# dnc_titreur.net
KiCad netlist of a schematic drawn in EAGLE
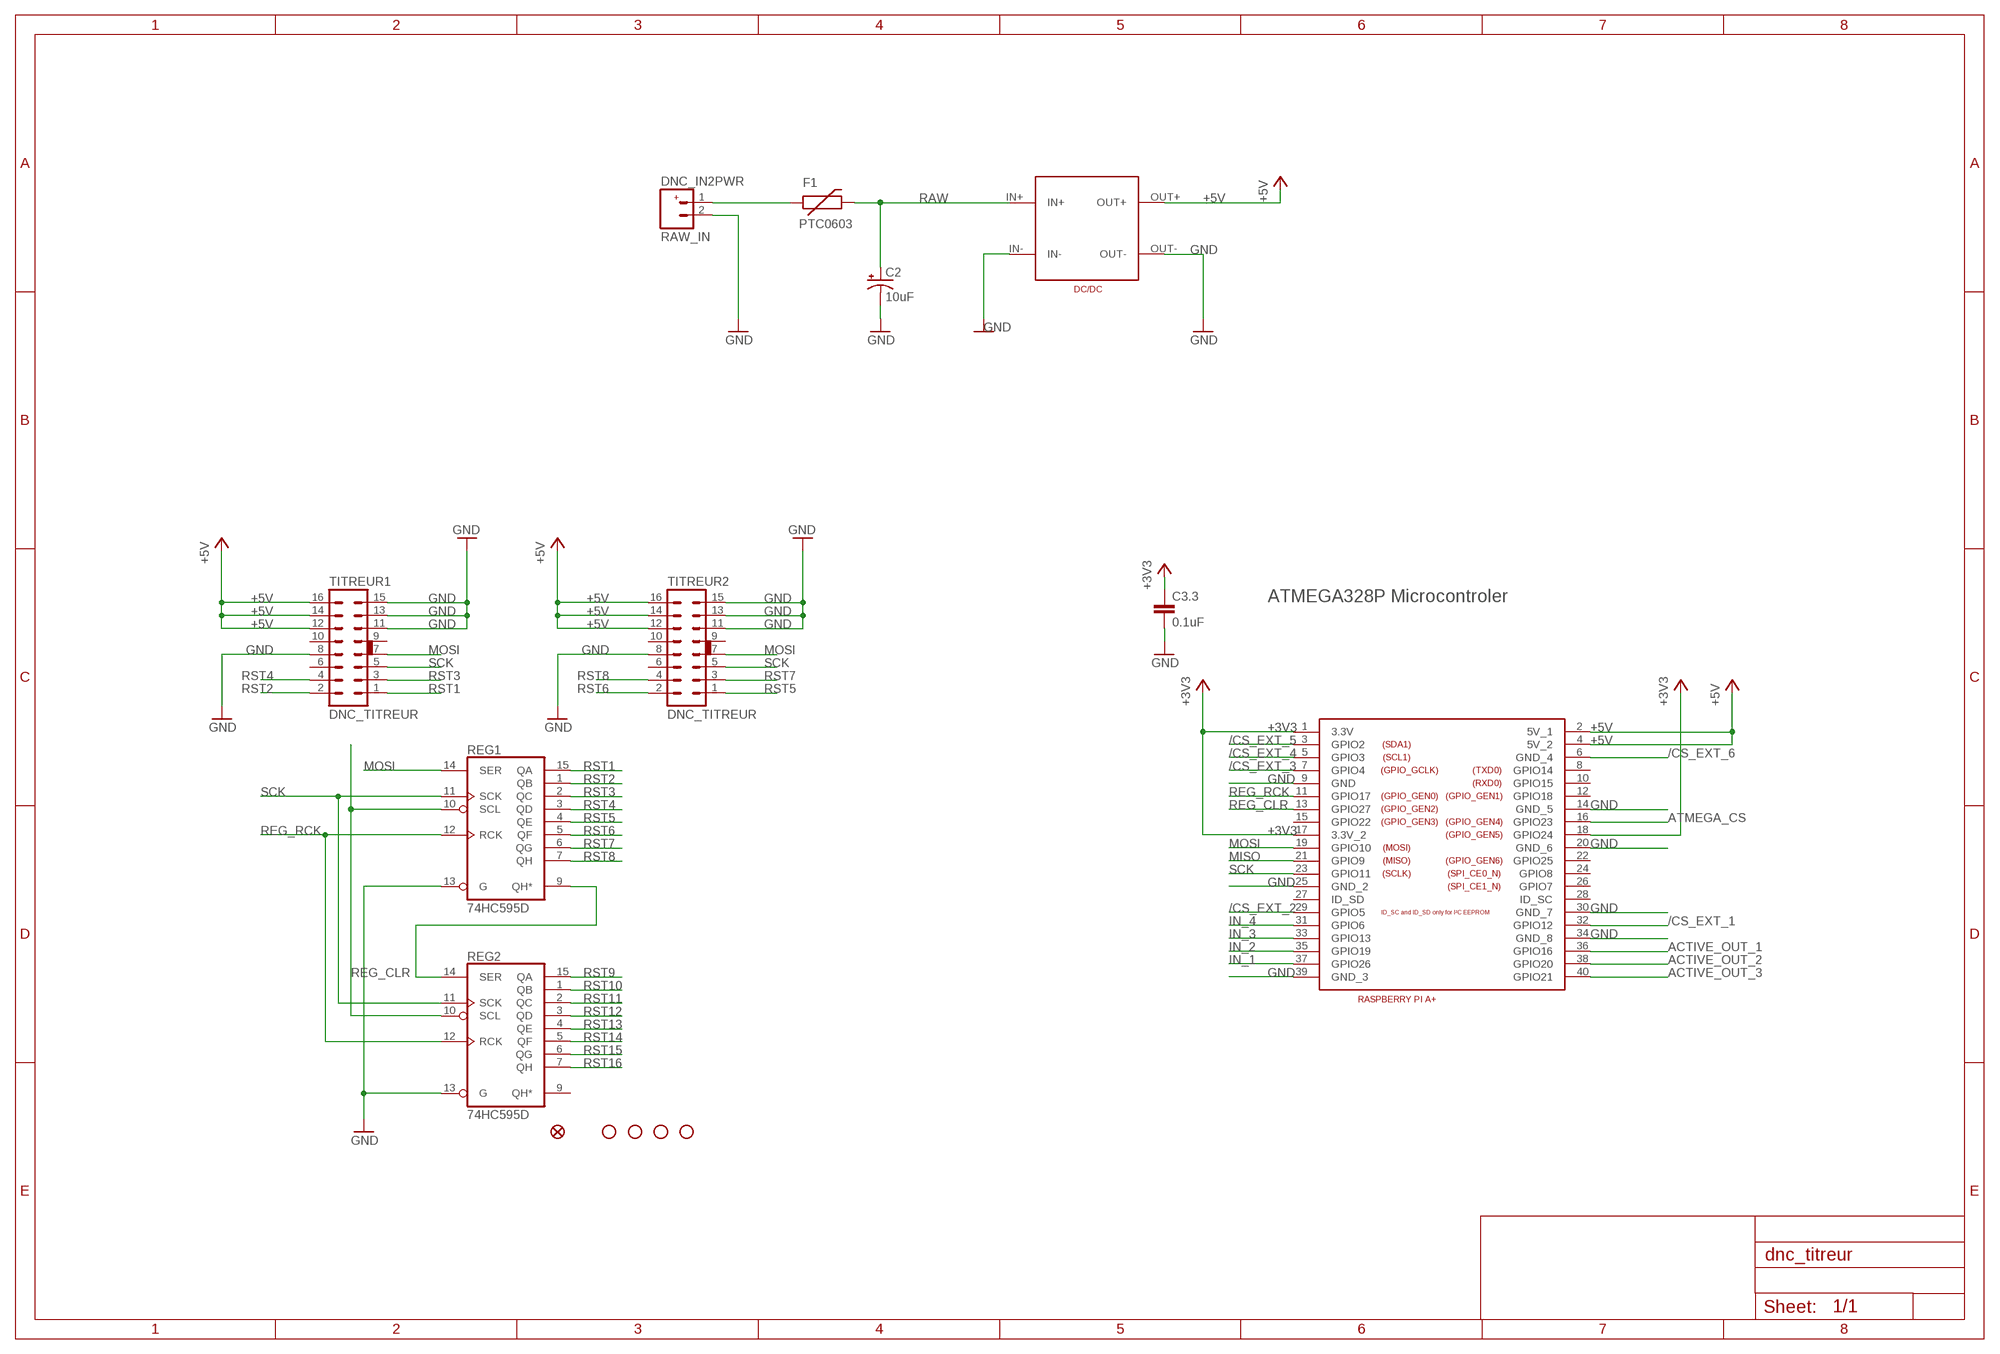
[diagram p0: schematic, sheet 1]

(export (version "E")
  (design (tool "Eeschema 10.0.6"))
  (components
    (comp (ref "C2")
      (value "10uF")
      (footprint "eagle-import:EIA3216")
      (libsource (lib "eagle-import") (part "CAP_POL1206"))
    )
    (comp (ref "C3.3")
      (value "0.1uF")
      (footprint "eagle-import:C0805")
      (libsource (lib "eagle-import") (part "C-EUC0805"))
    )
    (comp (ref "F1")
      (value "PTC0603")
      (footprint "eagle-import:0603")
      (libsource (lib "eagle-import") (part "PTC0603"))
    )
    (comp (ref "JP14")
      (value "FIDUCIAL1X2.5")
      (footprint "eagle-import:FIDUCIAL-1X2.5")
      (libsource (lib "eagle-import") (part "FIDUCIAL1X2.5"))
    )
    (comp (ref "JP15")
      (value "STAND-OFF")
      (footprint "eagle-import:STAND-OFF")
      (libsource (lib "eagle-import") (part "STAND-OFF"))
    )
    (comp (ref "JP16")
      (value "STAND-OFF")
      (footprint "eagle-import:STAND-OFF")
      (libsource (lib "eagle-import") (part "STAND-OFF"))
    )
    (comp (ref "JP17")
      (value "STAND-OFF")
      (footprint "eagle-import:STAND-OFF")
      (libsource (lib "eagle-import") (part "STAND-OFF"))
    )
    (comp (ref "JP18")
      (value "STAND-OFF")
      (footprint "eagle-import:STAND-OFF")
      (libsource (lib "eagle-import") (part "STAND-OFF"))
    )
    (comp (ref "RAW_IN")
      (value "DNC_IN2PWR")
      (footprint "eagle-import:DNC_IN2_PWR")
      (libsource (lib "eagle-import") (part "DNC_IN2PWR"))
    )
    (comp (ref "REG1")
      (value "74HC595D")
      (footprint "eagle-import:SO16")
      (libsource (lib "eagle-import") (part "74595DHC"))
    )
    (comp (ref "REG2")
      (value "74HC595D")
      (footprint "eagle-import:SO16")
      (libsource (lib "eagle-import") (part "74595DHC"))
    )
    (comp (ref "TITREUR1")
      (value "DNC_TITREUR")
      (footprint "eagle-import:DNC_TITREUR")
      (libsource (lib "eagle-import") (part "DNC_TITREUR"))
    )
    (comp (ref "TITREUR2")
      (value "DNC_TITREUR")
      (footprint "eagle-import:DNC_TITREUR")
      (libsource (lib "eagle-import") (part "DNC_TITREUR"))
    )
    (comp (ref "U$4")
      (value "RASPIA+")
      (footprint "eagle-import:RASPIA+")
      (libsource (lib "eagle-import") (part "RASPIA+"))
    )
    (comp (ref "U$5")
      (value "DC/DC_SEED")
      (footprint "eagle-import:DC_DC_SEED")
      (libsource (lib "eagle-import") (part "DC/DC_SEED"))
    )
  )
  (nets
    (net (code "1") (name "+3V3") (class "Default")
      (node (ref "C3.3") (pin "1") (pinfunction "1_1") (pintype "passive"))
      (node (ref "U$4") (pin "1") (pinfunction "3.3V_1") (pintype "bidirectional"))
      (node (ref "U$4") (pin "17") (pinfunction "3.3V_2_17") (pintype "bidirectional"))
      (node (ref "U$4") (pin "18") (pinfunction "GPIO24_18") (pintype "bidirectional"))
    )
    (net (code "2") (name "+5V") (class "Default")
      (node (ref "TITREUR1") (pin "12") (pinfunction "12_12") (pintype "passive"))
      (node (ref "TITREUR1") (pin "14") (pinfunction "14_14") (pintype "passive"))
      (node (ref "TITREUR1") (pin "16") (pinfunction "16_16") (pintype "passive"))
      (node (ref "TITREUR2") (pin "12") (pinfunction "12_12") (pintype "passive"))
      (node (ref "TITREUR2") (pin "14") (pinfunction "14_14") (pintype "passive"))
      (node (ref "TITREUR2") (pin "16") (pinfunction "16_16") (pintype "passive"))
      (node (ref "U$4") (pin "2") (pinfunction "5V_1_2") (pintype "bidirectional"))
      (node (ref "U$4") (pin "4") (pinfunction "5V_2_4") (pintype "bidirectional"))
      (node (ref "U$5") (pin "OUT+") (pinfunction "OUT+_OUT+") (pintype "bidirectional"))
    )
    (net (code "3") (name "/ACTIVE_OUT_1") (class "Default")
      (node (ref "U$4") (pin "36") (pinfunction "GPIO16_36") (pintype "bidirectional"))
    )
    (net (code "4") (name "/ACTIVE_OUT_2") (class "Default")
      (node (ref "U$4") (pin "38") (pinfunction "GPIO20_38") (pintype "bidirectional"))
    )
    (net (code "5") (name "/ACTIVE_OUT_3") (class "Default")
      (node (ref "U$4") (pin "40") (pinfunction "GPIO21_40") (pintype "bidirectional"))
    )
    (net (code "6") (name "/ATMEGA_CS") (class "Default")
      (node (ref "U$4") (pin "16") (pinfunction "GPIO23_16") (pintype "bidirectional"))
    )
    (net (code "7") (name "/IN_1") (class "Default")
      (node (ref "U$4") (pin "37") (pinfunction "GPIO26_37") (pintype "bidirectional"))
    )
    (net (code "8") (name "/IN_2") (class "Default")
      (node (ref "U$4") (pin "35") (pinfunction "GPIO19_35") (pintype "bidirectional"))
    )
    (net (code "9") (name "/IN_3") (class "Default")
      (node (ref "U$4") (pin "33") (pinfunction "GPIO13_33") (pintype "bidirectional"))
    )
    (net (code "10") (name "/IN_4") (class "Default")
      (node (ref "U$4") (pin "31") (pinfunction "GPIO6_31") (pintype "bidirectional"))
    )
    (net (code "11") (name "/MISO") (class "Default")
      (node (ref "U$4") (pin "21") (pinfunction "GPIO9_21") (pintype "bidirectional"))
    )
    (net (code "12") (name "/MOSI") (class "Default")
      (node (ref "REG1") (pin "14") (pinfunction "SER_14") (pintype "input"))
      (node (ref "TITREUR1") (pin "7") (pinfunction "7_7") (pintype "passive"))
      (node (ref "TITREUR2") (pin "7") (pinfunction "7_7") (pintype "passive"))
      (node (ref "U$4") (pin "19") (pinfunction "GPIO10_19") (pintype "bidirectional"))
    )
    (net (code "13") (name "/RAW") (class "Default")
      (node (ref "C2") (pin "A") (pinfunction "+_A") (pintype "passive"))
      (node (ref "F1") (pin "2") (pinfunction "2_2") (pintype "bidirectional"))
      (node (ref "U$5") (pin "IN+") (pinfunction "IN+_IN+") (pintype "bidirectional"))
    )
    (net (code "14") (name "/REG_CLR") (class "Default")
      (node (ref "REG1") (pin "10") (pinfunction "SCL_10") (pintype "input"))
      (node (ref "REG2") (pin "10") (pinfunction "SCL_10") (pintype "input"))
      (node (ref "U$4") (pin "13") (pinfunction "GPIO27_13") (pintype "bidirectional"))
    )
    (net (code "15") (name "/REG_RCK") (class "Default")
      (node (ref "REG1") (pin "12") (pinfunction "RCK_12") (pintype "input"))
      (node (ref "REG2") (pin "12") (pinfunction "RCK_12") (pintype "input"))
      (node (ref "U$4") (pin "11") (pinfunction "GPIO17_11") (pintype "bidirectional"))
    )
    (net (code "16") (name "/RST1") (class "Default")
      (node (ref "REG1") (pin "15") (pinfunction "QA_15") (pintype "tri_state"))
      (node (ref "TITREUR1") (pin "1") (pinfunction "1_1") (pintype "passive"))
    )
    (net (code "17") (name "/RST2") (class "Default")
      (node (ref "REG1") (pin "1") (pinfunction "QB_1") (pintype "tri_state"))
      (node (ref "TITREUR1") (pin "2") (pinfunction "2_2") (pintype "passive"))
    )
    (net (code "18") (name "/RST3") (class "Default")
      (node (ref "REG1") (pin "2") (pinfunction "QC_2") (pintype "tri_state"))
      (node (ref "TITREUR1") (pin "3") (pinfunction "3_3") (pintype "passive"))
    )
    (net (code "19") (name "/RST4") (class "Default")
      (node (ref "REG1") (pin "3") (pinfunction "QD_3") (pintype "tri_state"))
      (node (ref "TITREUR1") (pin "4") (pinfunction "4_4") (pintype "passive"))
    )
    (net (code "20") (name "/RST5") (class "Default")
      (node (ref "REG1") (pin "4") (pinfunction "QE_4") (pintype "tri_state"))
      (node (ref "TITREUR2") (pin "1") (pinfunction "1_1") (pintype "passive"))
    )
    (net (code "21") (name "/RST6") (class "Default")
      (node (ref "REG1") (pin "5") (pinfunction "QF_5") (pintype "tri_state"))
      (node (ref "TITREUR2") (pin "2") (pinfunction "2_2") (pintype "passive"))
    )
    (net (code "22") (name "/RST7") (class "Default")
      (node (ref "REG1") (pin "6") (pinfunction "QG_6") (pintype "tri_state"))
      (node (ref "TITREUR2") (pin "3") (pinfunction "3_3") (pintype "passive"))
    )
    (net (code "23") (name "/RST8") (class "Default")
      (node (ref "REG1") (pin "7") (pinfunction "QH_7") (pintype "tri_state"))
      (node (ref "TITREUR2") (pin "4") (pinfunction "4_4") (pintype "passive"))
    )
    (net (code "24") (name "/RST9") (class "Default")
      (node (ref "REG2") (pin "15") (pinfunction "QA_15") (pintype "tri_state"))
    )
    (net (code "25") (name "/RST10") (class "Default")
      (node (ref "REG2") (pin "1") (pinfunction "QB_1") (pintype "tri_state"))
    )
    (net (code "26") (name "/RST11") (class "Default")
      (node (ref "REG2") (pin "2") (pinfunction "QC_2") (pintype "tri_state"))
    )
    (net (code "27") (name "/RST12") (class "Default")
      (node (ref "REG2") (pin "3") (pinfunction "QD_3") (pintype "tri_state"))
    )
    (net (code "28") (name "/RST13") (class "Default")
      (node (ref "REG2") (pin "4") (pinfunction "QE_4") (pintype "tri_state"))
    )
    (net (code "29") (name "/RST14") (class "Default")
      (node (ref "REG2") (pin "5") (pinfunction "QF_5") (pintype "tri_state"))
    )
    (net (code "30") (name "/RST15") (class "Default")
      (node (ref "REG2") (pin "6") (pinfunction "QG_6") (pintype "tri_state"))
    )
    (net (code "31") (name "/RST16") (class "Default")
      (node (ref "REG2") (pin "7") (pinfunction "QH_7") (pintype "tri_state"))
    )
    (net (code "32") (name "/SCK") (class "Default")
      (node (ref "REG1") (pin "11") (pinfunction "SCK_11") (pintype "input"))
      (node (ref "REG2") (pin "11") (pinfunction "SCK_11") (pintype "input"))
      (node (ref "TITREUR1") (pin "5") (pinfunction "5_5") (pintype "passive"))
      (node (ref "TITREUR2") (pin "5") (pinfunction "5_5") (pintype "passive"))
      (node (ref "U$4") (pin "23") (pinfunction "GPIO11_23") (pintype "bidirectional"))
    )
    (net (code "33") (name "/{slash}CS_EXT_1") (class "Default")
      (node (ref "U$4") (pin "32") (pinfunction "GPIO12_32") (pintype "bidirectional"))
    )
    (net (code "34") (name "/{slash}CS_EXT_2") (class "Default")
      (node (ref "U$4") (pin "29") (pinfunction "GPIO5_29") (pintype "bidirectional"))
    )
    (net (code "35") (name "/{slash}CS_EXT_3") (class "Default")
      (node (ref "U$4") (pin "7") (pinfunction "GPIO4_7") (pintype "bidirectional"))
    )
    (net (code "36") (name "/{slash}CS_EXT_4") (class "Default")
      (node (ref "U$4") (pin "5") (pinfunction "GPIO3_5") (pintype "bidirectional"))
    )
    (net (code "37") (name "/{slash}CS_EXT_5") (class "Default")
      (node (ref "U$4") (pin "3") (pinfunction "GPIO2_3") (pintype "bidirectional"))
    )
    (net (code "38") (name "/{slash}CS_EXT_6") (class "Default")
      (node (ref "U$4") (pin "6") (pinfunction "GND_4_6") (pintype "bidirectional"))
    )
    (net (code "39") (name "GND") (class "Default")
      (node (ref "C2") (pin "C") (pinfunction "-_C") (pintype "passive"))
      (node (ref "C3.3") (pin "2") (pinfunction "2_2") (pintype "passive"))
      (node (ref "RAW_IN") (pin "2") (pinfunction "2_2") (pintype "passive"))
      (node (ref "REG1") (pin "13") (pinfunction "G_13") (pintype "input"))
      (node (ref "REG2") (pin "13") (pinfunction "G_13") (pintype "input"))
      (node (ref "TITREUR1") (pin "11") (pinfunction "11_11") (pintype "passive"))
      (node (ref "TITREUR1") (pin "13") (pinfunction "13_13") (pintype "passive"))
      (node (ref "TITREUR1") (pin "15") (pinfunction "15_15") (pintype "passive"))
      (node (ref "TITREUR1") (pin "8") (pinfunction "8_8") (pintype "passive"))
      (node (ref "TITREUR2") (pin "11") (pinfunction "11_11") (pintype "passive"))
      (node (ref "TITREUR2") (pin "13") (pinfunction "13_13") (pintype "passive"))
      (node (ref "TITREUR2") (pin "15") (pinfunction "15_15") (pintype "passive"))
      (node (ref "TITREUR2") (pin "8") (pinfunction "8_8") (pintype "passive"))
      (node (ref "U$4") (pin "14") (pinfunction "GND_5_14") (pintype "bidirectional"))
      (node (ref "U$4") (pin "20") (pinfunction "GND_6_20") (pintype "bidirectional"))
      (node (ref "U$4") (pin "25") (pinfunction "GND_2_25") (pintype "bidirectional"))
      (node (ref "U$4") (pin "30") (pinfunction "GND_7_30") (pintype "bidirectional"))
      (node (ref "U$4") (pin "34") (pinfunction "GND_8_34") (pintype "bidirectional"))
      (node (ref "U$4") (pin "39") (pinfunction "GND_3_39") (pintype "bidirectional"))
      (node (ref "U$4") (pin "9") (pinfunction "GND_9") (pintype "bidirectional"))
      (node (ref "U$5") (pin "IN-") (pinfunction "IN-_IN-") (pintype "bidirectional"))
      (node (ref "U$5") (pin "OUT-") (pinfunction "OUT-_OUT-") (pintype "bidirectional"))
    )
    (net (code "40") (name "Net-(F1-Pad1)") (class "Default")
      (node (ref "F1") (pin "1") (pinfunction "1_1") (pintype "bidirectional"))
      (node (ref "RAW_IN") (pin "1") (pinfunction "1_1") (pintype "passive"))
    )
    (net (code "41") (name "Net-(REG1A-QH*)") (class "Default")
      (node (ref "REG1") (pin "9") (pinfunction "QH*_9") (pintype "tri_state"))
      (node (ref "REG2") (pin "14") (pinfunction "SER_14") (pintype "input"))
    )
    (net (code "42") (name "unconnected-(REG2A-QH*-Pad9)") (class "Default")
      (node (ref "REG2") (pin "9") (pinfunction "QH*_9") (pintype "tri_state"))
    )
    (net (code "43") (name "unconnected-(TITREUR1-Pad6)") (class "Default")
      (node (ref "TITREUR1") (pin "6") (pinfunction "6_6") (pintype "passive"))
    )
    (net (code "44") (name "unconnected-(TITREUR1-Pad9)") (class "Default")
      (node (ref "TITREUR1") (pin "9") (pinfunction "9_9") (pintype "passive"))
    )
    (net (code "45") (name "unconnected-(TITREUR1-Pad10)") (class "Default")
      (node (ref "TITREUR1") (pin "10") (pinfunction "10_10") (pintype "passive"))
    )
    (net (code "46") (name "unconnected-(TITREUR2-Pad6)") (class "Default")
      (node (ref "TITREUR2") (pin "6") (pinfunction "6_6") (pintype "passive"))
    )
    (net (code "47") (name "unconnected-(TITREUR2-Pad9)") (class "Default")
      (node (ref "TITREUR2") (pin "9") (pinfunction "9_9") (pintype "passive"))
    )
    (net (code "48") (name "unconnected-(TITREUR2-Pad10)") (class "Default")
      (node (ref "TITREUR2") (pin "10") (pinfunction "10_10") (pintype "passive"))
    )
    (net (code "49") (name "unconnected-(U$4-GPIO7-Pad26)") (class "Default")
      (node (ref "U$4") (pin "26") (pinfunction "GPIO7_26") (pintype "bidirectional"))
    )
    (net (code "50") (name "unconnected-(U$4-GPIO8-Pad24)") (class "Default")
      (node (ref "U$4") (pin "24") (pinfunction "GPIO8_24") (pintype "bidirectional"))
    )
    (net (code "51") (name "unconnected-(U$4-GPIO14-Pad8)") (class "Default")
      (node (ref "U$4") (pin "8") (pinfunction "GPIO14_8") (pintype "bidirectional"))
    )
    (net (code "52") (name "unconnected-(U$4-GPIO15-Pad10)") (class "Default")
      (node (ref "U$4") (pin "10") (pinfunction "GPIO15_10") (pintype "bidirectional"))
    )
    (net (code "53") (name "unconnected-(U$4-GPIO18-Pad12)") (class "Default")
      (node (ref "U$4") (pin "12") (pinfunction "GPIO18_12") (pintype "bidirectional"))
    )
    (net (code "54") (name "unconnected-(U$4-GPIO22-Pad15)") (class "Default")
      (node (ref "U$4") (pin "15") (pinfunction "GPIO22_15") (pintype "bidirectional"))
    )
    (net (code "55") (name "unconnected-(U$4-GPIO25-Pad22)") (class "Default")
      (node (ref "U$4") (pin "22") (pinfunction "GPIO25_22") (pintype "bidirectional"))
    )
    (net (code "56") (name "unconnected-(U$4-ID_SC-Pad28)") (class "Default")
      (node (ref "U$4") (pin "28") (pinfunction "ID_SC_28") (pintype "bidirectional"))
    )
    (net (code "57") (name "unconnected-(U$4-ID_SD-Pad27)") (class "Default")
      (node (ref "U$4") (pin "27") (pinfunction "ID_SD_27") (pintype "bidirectional"))
    )
  )
)
